# Outputs.net
KiCad netlist of a schematic drawn in Altium Designer
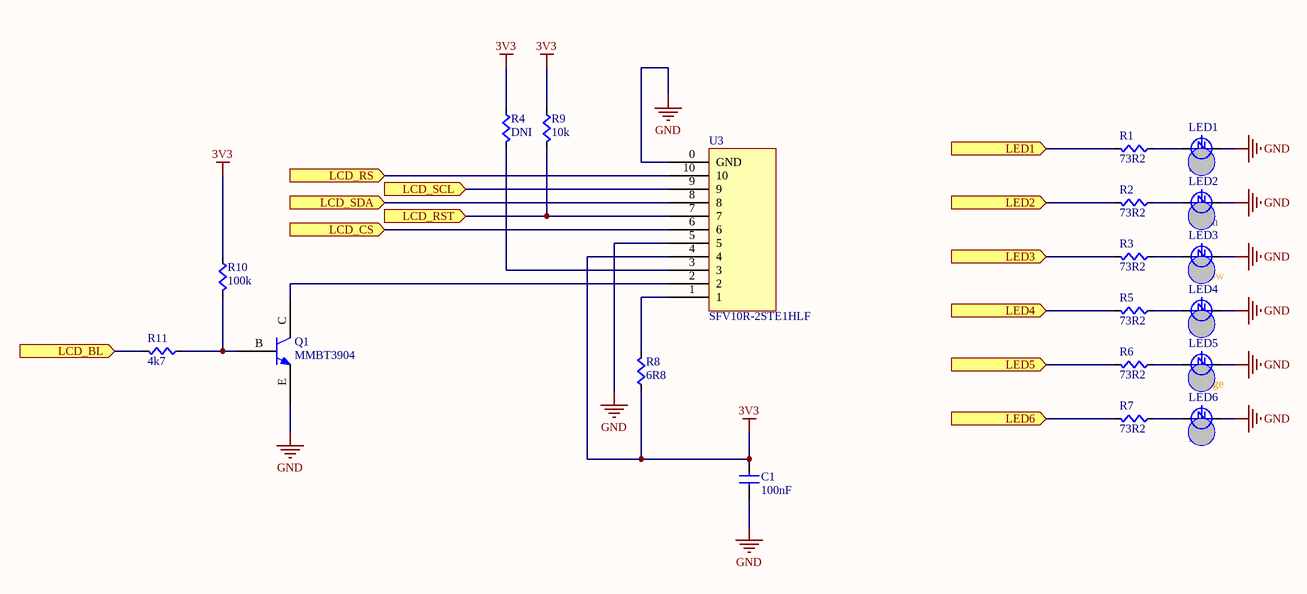
[diagram p0: Outputs.SchDoc]

(export (version "E")
  (design (tool "Eeschema 10.0.6"))
  (components
    (comp (ref "C1")
      (value "100nF")
      (footprint "CAPC0603")
      (fields (field (name "Comment") "Cap"))
      (libsource (lib "SubjuGator8") (part "Cap"))
    )
    (comp (ref "LED1")
      (value "LED")
      (footprint "LED0603")
      (fields (field (name "COLOR") "Red"))
      (libsource (lib "SubjuGator8") (part "LED"))
    )
    (comp (ref "LED2")
      (value "LED")
      (footprint "LED0603")
      (fields (field (name "COLOR") "Green"))
      (libsource (lib "SubjuGator8") (part "LED"))
    )
    (comp (ref "LED3")
      (value "LED")
      (footprint "LED0603")
      (fields (field (name "COLOR") "Yellow"))
      (libsource (lib "SubjuGator8") (part "LED"))
    )
    (comp (ref "LED4")
      (value "LED")
      (footprint "LED0603")
      (fields (field (name "COLOR") "Pink"))
      (libsource (lib "SubjuGator8") (part "LED"))
    )
    (comp (ref "LED5")
      (value "LED")
      (footprint "LED0603")
      (fields (field (name "COLOR") "Orange"))
      (libsource (lib "SubjuGator8") (part "LED"))
    )
    (comp (ref "LED6")
      (value "LED")
      (footprint "LED0603")
      (fields (field (name "COLOR") "Blue"))
      (libsource (lib "SubjuGator8") (part "LED"))
    )
    (comp (ref "Q1")
      (value "MMBT3904")
      (footprint "MMBT3904")
      (description "TRANS NPN 40V 0.2A SOT-23")
      (libsource (lib "SubjuGator8") (part "MMBT3904"))
    )
    (comp (ref "R1")
      (value "73R2")
      (footprint "RES0603")
      (fields (field (name "Comment") "Res"))
      (libsource (lib "SubjuGator8") (part "Res"))
    )
    (comp (ref "R2")
      (value "73R2")
      (footprint "RES0603")
      (fields (field (name "Comment") "Res"))
      (libsource (lib "SubjuGator8") (part "Res"))
    )
    (comp (ref "R3")
      (value "73R2")
      (footprint "RES0603")
      (fields (field (name "Comment") "Res"))
      (libsource (lib "SubjuGator8") (part "Res"))
    )
    (comp (ref "R4")
      (value "DNI")
      (footprint "RES0603")
      (fields (field (name "Comment") "Res"))
      (libsource (lib "SubjuGator8") (part "Res"))
    )
    (comp (ref "R5")
      (value "73R2")
      (footprint "RES0603")
      (fields (field (name "Comment") "Res"))
      (libsource (lib "SubjuGator8") (part "Res"))
    )
    (comp (ref "R6")
      (value "73R2")
      (footprint "RES0603")
      (fields (field (name "Comment") "Res"))
      (libsource (lib "SubjuGator8") (part "Res"))
    )
    (comp (ref "R7")
      (value "73R2")
      (footprint "RES0603")
      (fields (field (name "Comment") "Res"))
      (libsource (lib "SubjuGator8") (part "Res"))
    )
    (comp (ref "R8")
      (value "6R8")
      (footprint "RES0603")
      (fields (field (name "Comment") "Res"))
      (libsource (lib "SubjuGator8") (part "Res"))
    )
    (comp (ref "R9")
      (value "10k")
      (footprint "RES0603")
      (fields (field (name "Comment") "Res"))
      (libsource (lib "SubjuGator8") (part "Res"))
    )
    (comp (ref "R10")
      (value "100k")
      (footprint "RES0603")
      (fields (field (name "Comment") "Res"))
      (libsource (lib "SubjuGator8") (part "Res"))
    )
    (comp (ref "R11")
      (value "4k7")
      (footprint "RES0603")
      (fields (field (name "Comment") "Res"))
      (libsource (lib "SubjuGator8") (part "Res"))
    )
    (comp (ref "U3")
      (value "SFV10R-2STE1HLF")
      (footprint "SFV10R-2STE1HLF")
      (description "CONN FFC TOP 10POS 0.50MM R/A")
      (libsource (lib "SubjuGator8") (part "SFV10R-2STE1HLF"))
    )
  )
  (nets
    (net (code "1") (name "/LCD_BL") (class "Default")
      (node (ref "R11") (pin "1") (pinfunction "A_1") (pintype "passive"))
    )
    (net (code "2") (name "/LCD_CS") (class "Default")
      (node (ref "U3") (pin "6") (pinfunction "6_6") (pintype "passive"))
    )
    (net (code "3") (name "/LCD_RS") (class "Default")
      (node (ref "U3") (pin "10") (pinfunction "10_10") (pintype "passive"))
    )
    (net (code "4") (name "/LCD_RST") (class "Default")
      (node (ref "R9") (pin "1") (pinfunction "A_1") (pintype "passive"))
      (node (ref "U3") (pin "7") (pinfunction "7_7") (pintype "passive"))
    )
    (net (code "5") (name "/LCD_SCL") (class "Default")
      (node (ref "U3") (pin "9") (pinfunction "9_9") (pintype "passive"))
    )
    (net (code "6") (name "/LCD_SDA") (class "Default")
      (node (ref "U3") (pin "8") (pinfunction "8_8") (pintype "passive"))
    )
    (net (code "7") (name "/LED1") (class "Default")
      (node (ref "R1") (pin "1") (pinfunction "A_1") (pintype "passive"))
    )
    (net (code "8") (name "/LED2") (class "Default")
      (node (ref "R2") (pin "1") (pinfunction "A_1") (pintype "passive"))
    )
    (net (code "9") (name "/LED3") (class "Default")
      (node (ref "R3") (pin "1") (pinfunction "A_1") (pintype "passive"))
    )
    (net (code "10") (name "/LED4") (class "Default")
      (node (ref "R5") (pin "1") (pinfunction "A_1") (pintype "passive"))
    )
    (net (code "11") (name "/LED5") (class "Default")
      (node (ref "R6") (pin "1") (pinfunction "A_1") (pintype "passive"))
    )
    (net (code "12") (name "/LED6") (class "Default")
      (node (ref "R7") (pin "1") (pinfunction "A_1") (pintype "passive"))
    )
    (net (code "13") (name "3V3") (class "Default")
      (node (ref "C1") (pin "1") (pinfunction "A_1") (pintype "passive"))
      (node (ref "R10") (pin "2") (pinfunction "B_2") (pintype "passive"))
      (node (ref "R4") (pin "2") (pinfunction "B_2") (pintype "passive"))
      (node (ref "R8") (pin "2") (pinfunction "B_2") (pintype "passive"))
      (node (ref "R9") (pin "2") (pinfunction "B_2") (pintype "passive"))
      (node (ref "U3") (pin "4") (pinfunction "4_4") (pintype "passive"))
    )
    (net (code "14") (name "GND") (class "Default")
      (node (ref "C1") (pin "2") (pinfunction "B_2") (pintype "passive"))
      (node (ref "LED1") (pin "C") (pinfunction "C_C") (pintype "passive"))
      (node (ref "LED2") (pin "C") (pinfunction "C_C") (pintype "passive"))
      (node (ref "LED3") (pin "C") (pinfunction "C_C") (pintype "passive"))
      (node (ref "LED4") (pin "C") (pinfunction "C_C") (pintype "passive"))
      (node (ref "LED5") (pin "C") (pinfunction "C_C") (pintype "passive"))
      (node (ref "LED6") (pin "C") (pinfunction "C_C") (pintype "passive"))
      (node (ref "Q1") (pin "E") (pinfunction "E_E") (pintype "passive"))
      (node (ref "U3") (pin "0") (pinfunction "GND_0") (pintype "passive"))
      (node (ref "U3") (pin "5") (pinfunction "5_5") (pintype "passive"))
    )
    (net (code "15") (name "Net-(Q1-PadC)") (class "Default")
      (node (ref "Q1") (pin "C") (pinfunction "C_C") (pintype "passive"))
      (node (ref "U3") (pin "2") (pinfunction "2_2") (pintype "passive"))
    )
    (net (code "16") (name "Net-(R1-B)") (class "Default")
      (node (ref "LED1") (pin "A") (pinfunction "A_A") (pintype "passive"))
      (node (ref "R1") (pin "2") (pinfunction "B_2") (pintype "passive"))
    )
    (net (code "17") (name "Net-(R2-B)") (class "Default")
      (node (ref "LED2") (pin "A") (pinfunction "A_A") (pintype "passive"))
      (node (ref "R2") (pin "2") (pinfunction "B_2") (pintype "passive"))
    )
    (net (code "18") (name "Net-(R3-B)") (class "Default")
      (node (ref "LED3") (pin "A") (pinfunction "A_A") (pintype "passive"))
      (node (ref "R3") (pin "2") (pinfunction "B_2") (pintype "passive"))
    )
    (net (code "19") (name "Net-(R4-A)") (class "Default")
      (node (ref "R4") (pin "1") (pinfunction "A_1") (pintype "passive"))
      (node (ref "U3") (pin "3") (pinfunction "3_3") (pintype "passive"))
    )
    (net (code "20") (name "Net-(R5-B)") (class "Default")
      (node (ref "LED4") (pin "A") (pinfunction "A_A") (pintype "passive"))
      (node (ref "R5") (pin "2") (pinfunction "B_2") (pintype "passive"))
    )
    (net (code "21") (name "Net-(R6-B)") (class "Default")
      (node (ref "LED5") (pin "A") (pinfunction "A_A") (pintype "passive"))
      (node (ref "R6") (pin "2") (pinfunction "B_2") (pintype "passive"))
    )
    (net (code "22") (name "Net-(R7-B)") (class "Default")
      (node (ref "LED6") (pin "A") (pinfunction "A_A") (pintype "passive"))
      (node (ref "R7") (pin "2") (pinfunction "B_2") (pintype "passive"))
    )
    (net (code "23") (name "Net-(R8-A)") (class "Default")
      (node (ref "R8") (pin "1") (pinfunction "A_1") (pintype "passive"))
      (node (ref "U3") (pin "1") (pinfunction "1_1") (pintype "passive"))
    )
    (net (code "24") (name "Net-(R10-A)") (class "Default")
      (node (ref "Q1") (pin "B") (pinfunction "B_B") (pintype "passive"))
      (node (ref "R10") (pin "1") (pinfunction "A_1") (pintype "passive"))
      (node (ref "R11") (pin "2") (pinfunction "B_2") (pintype "passive"))
    )
  )
)
